# ME433_sunyue.net
KiCad netlist of a schematic drawn in EAGLE
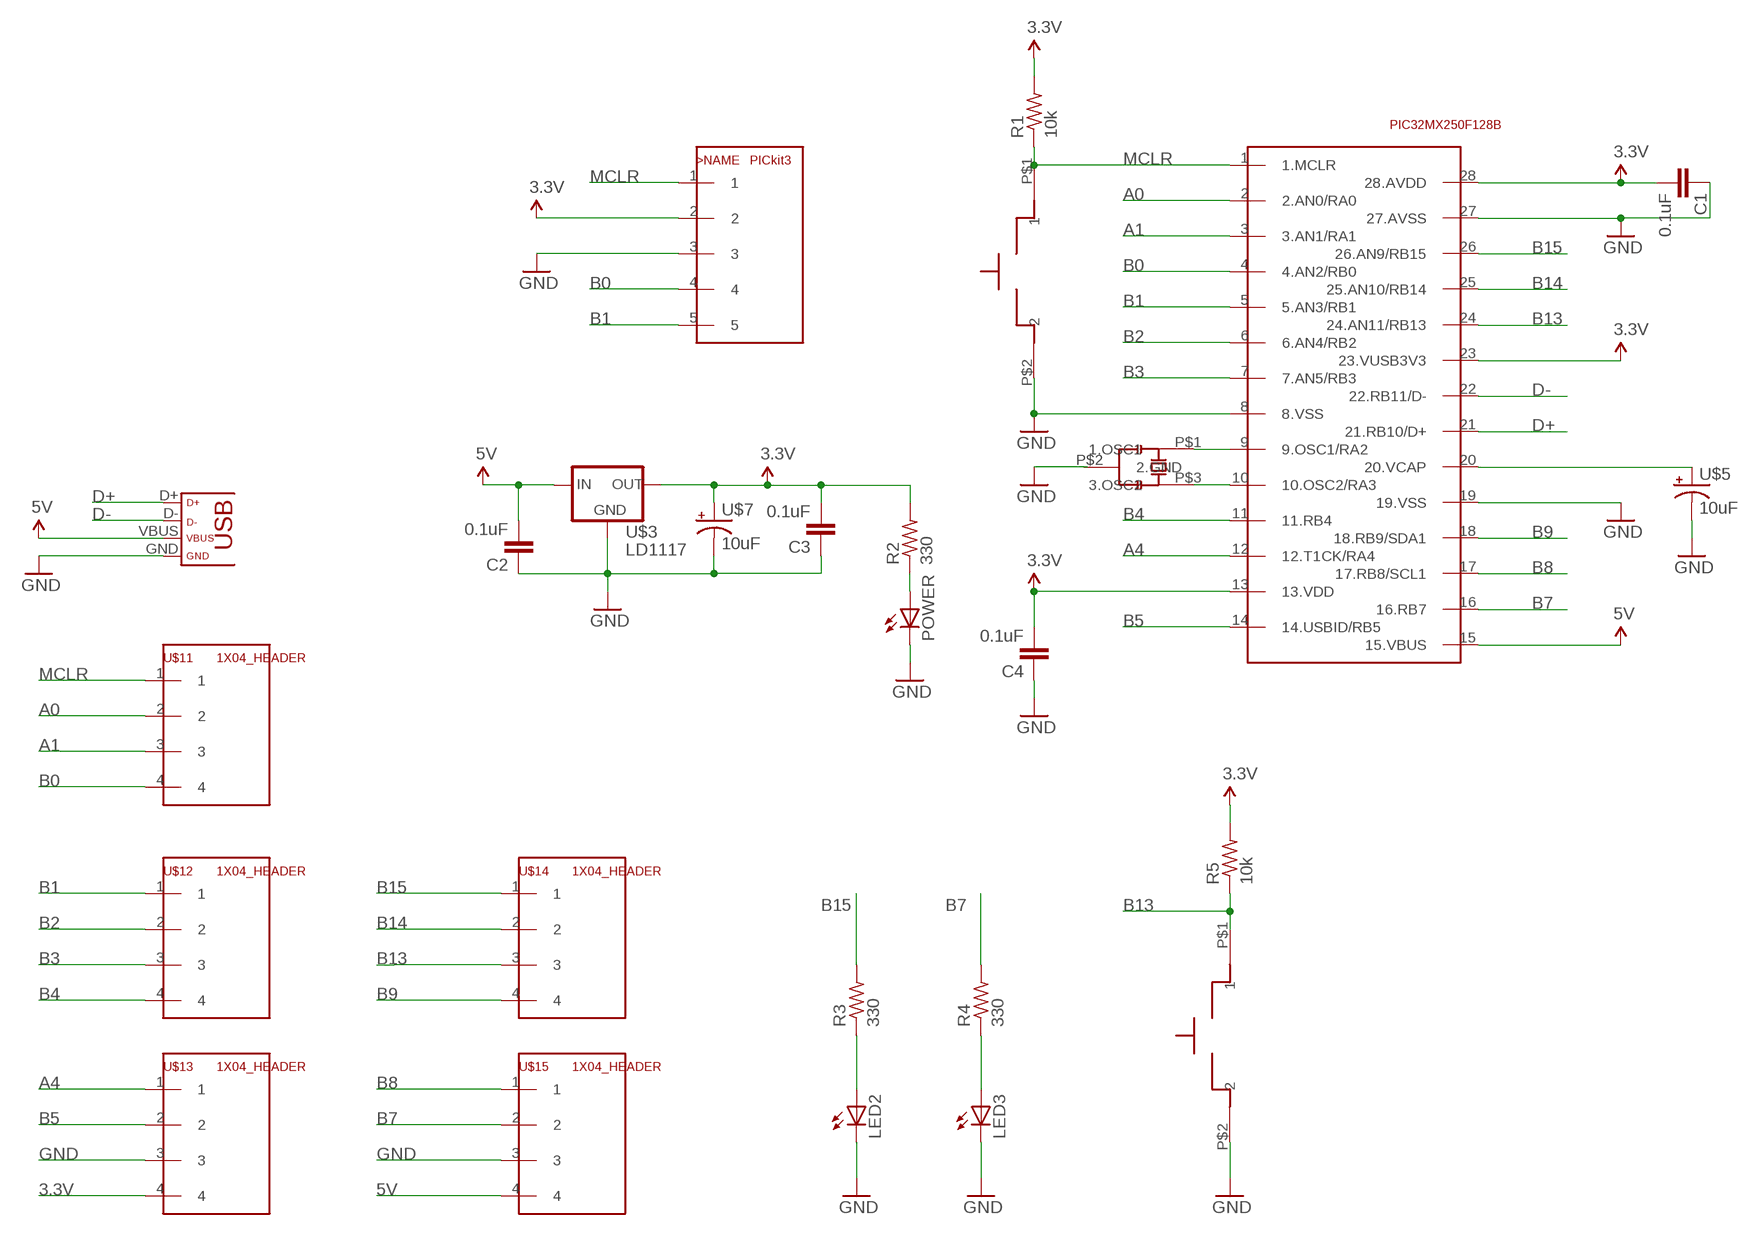
[diagram p0: schematic, sheet 1]

(export (version "E")
  (design (tool "Eeschema 10.0.6"))
  (components
    (comp (ref ">NAME")
      (value "PICkit3")
      (footprint "eagle-import:1X05")
      (libsource (lib "eagle-import") (part "1X05_HEADER"))
    )
    (comp (ref "C1")
      (value "0.1uF")
      (footprint "eagle-import:C025-025X050")
      (libsource (lib "eagle-import") (part "C-EU025-025X050"))
    )
    (comp (ref "C2")
      (value "0.1uF")
      (footprint "eagle-import:C025-025X050")
      (libsource (lib "eagle-import") (part "C-EU025-025X050"))
    )
    (comp (ref "C3")
      (value "0.1uF")
      (footprint "eagle-import:C025-025X050")
      (libsource (lib "eagle-import") (part "C-EU025-025X050"))
    )
    (comp (ref "C4")
      (value "0.1uF")
      (footprint "eagle-import:C025-025X050")
      (libsource (lib "eagle-import") (part "C-EU025-025X050"))
    )
    (comp (ref "LED2")
      (value "LED3MM")
      (footprint "eagle-import:LED3MM")
      (libsource (lib "eagle-import") (part "LED3MM"))
    )
    (comp (ref "LED3")
      (value "LED3MM")
      (footprint "eagle-import:LED3MM")
      (libsource (lib "eagle-import") (part "LED3MM"))
    )
    (comp (ref "POWER")
      (value "LED3MM")
      (footprint "eagle-import:LED3MM")
      (libsource (lib "eagle-import") (part "LED3MM"))
    )
    (comp (ref "R1")
      (value "10k")
      (footprint "eagle-import:0207_10")
      (libsource (lib "eagle-import") (part "R-US_0207/10"))
    )
    (comp (ref "R2")
      (value "330")
      (footprint "eagle-import:0207_10")
      (libsource (lib "eagle-import") (part "R-US_0207/10"))
    )
    (comp (ref "R3")
      (value "330")
      (footprint "eagle-import:0207_10")
      (libsource (lib "eagle-import") (part "R-US_0207/10"))
    )
    (comp (ref "R4")
      (value "330")
      (footprint "eagle-import:0207_10")
      (libsource (lib "eagle-import") (part "R-US_0207/10"))
    )
    (comp (ref "R5")
      (value "10k")
      (footprint "eagle-import:0207_10")
      (libsource (lib "eagle-import") (part "R-US_0207/10"))
    )
    (comp (ref "RESET")
      (value "RESET")
      (footprint "eagle-import:BUTTON")
      (libsource (lib "eagle-import") (part "BUTTON"))
    )
    (comp (ref "U$1")
      (value "PIC32MX250F128B")
      (footprint "eagle-import:DIL28-3")
      (libsource (lib "eagle-import") (part "PIC32MX250F128B"))
    )
    (comp (ref "U$2")
      (value "CRYSTAL")
      (footprint "eagle-import:CRYSTAL")
      (libsource (lib "eagle-import") (part "CRYSTAL"))
    )
    (comp (ref "U$3")
      (value "LD1117")
      (footprint "eagle-import:TO220")
      (libsource (lib "eagle-import") (part "LD1117"))
    )
    (comp (ref "U$5")
      (value "10uF")
      (footprint "eagle-import:CAP_POL_D")
      (libsource (lib "eagle-import") (part "CAP_POL"))
    )
    (comp (ref "U$7")
      (value "10uF")
      (footprint "eagle-import:CAP_POL_D")
      (libsource (lib "eagle-import") (part "CAP_POL"))
    )
    (comp (ref "U$9")
      (value "USB")
      (footprint "eagle-import:USB-MINIB")
      (libsource (lib "eagle-import") (part "USB"))
    )
    (comp (ref "U$11")
      (value "1X04_HEADER")
      (footprint "eagle-import:1X04")
      (libsource (lib "eagle-import") (part "1X04_HEADER"))
    )
    (comp (ref "U$12")
      (value "1X04_HEADER")
      (footprint "eagle-import:1X04")
      (libsource (lib "eagle-import") (part "1X04_HEADER"))
    )
    (comp (ref "U$13")
      (value "1X04_HEADER")
      (footprint "eagle-import:1X04")
      (libsource (lib "eagle-import") (part "1X04_HEADER"))
    )
    (comp (ref "U$14")
      (value "1X04_HEADER")
      (footprint "eagle-import:1X04")
      (libsource (lib "eagle-import") (part "1X04_HEADER"))
    )
    (comp (ref "U$15")
      (value "1X04_HEADER")
      (footprint "eagle-import:1X04")
      (libsource (lib "eagle-import") (part "1X04_HEADER"))
    )
    (comp (ref "USER")
      (value "BUTTON")
      (footprint "eagle-import:BUTTON")
      (libsource (lib "eagle-import") (part "BUTTON"))
    )
  )
  (nets
    (net (code "1") (name "/A0") (class "Default")
      (node (ref "U$1") (pin "2") (pinfunction "2.AN0/RA0_2") (pintype "bidirectional"))
      (node (ref "U$11") (pin "2") (pinfunction "2_2") (pintype "bidirectional"))
    )
    (net (code "2") (name "/A1") (class "Default")
      (node (ref "U$1") (pin "3") (pinfunction "3.AN1/RA1_3") (pintype "bidirectional"))
      (node (ref "U$11") (pin "3") (pinfunction "3_3") (pintype "bidirectional"))
    )
    (net (code "3") (name "/A4") (class "Default")
      (node (ref "U$1") (pin "12") (pinfunction "12.T1CK/RA4_12") (pintype "bidirectional"))
      (node (ref "U$13") (pin "1") (pinfunction "1_1") (pintype "bidirectional"))
    )
    (net (code "4") (name "/B0") (class "Default")
      (node (ref ">NAME") (pin "4") (pinfunction "4_4") (pintype "bidirectional"))
      (node (ref "U$1") (pin "4") (pinfunction "4.AN2/RB0_4") (pintype "bidirectional"))
      (node (ref "U$11") (pin "4") (pinfunction "4_4") (pintype "bidirectional"))
    )
    (net (code "5") (name "/B1") (class "Default")
      (node (ref ">NAME") (pin "5") (pinfunction "5_5") (pintype "bidirectional"))
      (node (ref "U$1") (pin "5") (pinfunction "5.AN3/RB1_5") (pintype "bidirectional"))
      (node (ref "U$12") (pin "1") (pinfunction "1_1") (pintype "bidirectional"))
    )
    (net (code "6") (name "/B2") (class "Default")
      (node (ref "U$1") (pin "6") (pinfunction "6.AN4/RB2_6") (pintype "bidirectional"))
      (node (ref "U$12") (pin "2") (pinfunction "2_2") (pintype "bidirectional"))
    )
    (net (code "7") (name "/B3") (class "Default")
      (node (ref "U$1") (pin "7") (pinfunction "7.AN5/RB3_7") (pintype "bidirectional"))
      (node (ref "U$12") (pin "3") (pinfunction "3_3") (pintype "bidirectional"))
    )
    (net (code "8") (name "/B4") (class "Default")
      (node (ref "U$1") (pin "11") (pinfunction "11.RB4_11") (pintype "bidirectional"))
      (node (ref "U$12") (pin "4") (pinfunction "4_4") (pintype "bidirectional"))
    )
    (net (code "9") (name "/B5") (class "Default")
      (node (ref "U$1") (pin "14") (pinfunction "14.USBID/RB5_14") (pintype "bidirectional"))
      (node (ref "U$13") (pin "2") (pinfunction "2_2") (pintype "bidirectional"))
    )
    (net (code "10") (name "/B7") (class "Default")
      (node (ref "R4") (pin "2") (pinfunction "2_2") (pintype "passive"))
      (node (ref "U$1") (pin "16") (pinfunction "16.RB7_16") (pintype "bidirectional"))
      (node (ref "U$15") (pin "2") (pinfunction "2_2") (pintype "bidirectional"))
    )
    (net (code "11") (name "/B8") (class "Default")
      (node (ref "U$1") (pin "17") (pinfunction "17.RB8/SCL1_17") (pintype "bidirectional"))
      (node (ref "U$15") (pin "1") (pinfunction "1_1") (pintype "bidirectional"))
    )
    (net (code "12") (name "/B9") (class "Default")
      (node (ref "U$1") (pin "18") (pinfunction "18.RB9/SDA1_18") (pintype "bidirectional"))
      (node (ref "U$14") (pin "4") (pinfunction "4_4") (pintype "bidirectional"))
    )
    (net (code "13") (name "/B13") (class "Default")
      (node (ref "R5") (pin "1") (pinfunction "1_1") (pintype "passive"))
      (node (ref "U$1") (pin "24") (pinfunction "24.AN11/RB13_24") (pintype "bidirectional"))
      (node (ref "U$14") (pin "3") (pinfunction "3_3") (pintype "bidirectional"))
      (node (ref "USER") (pin "P$1") (pinfunction "1_P$1") (pintype "bidirectional"))
    )
    (net (code "14") (name "/B14") (class "Default")
      (node (ref "U$1") (pin "25") (pinfunction "25.AN10/RB14_25") (pintype "bidirectional"))
      (node (ref "U$14") (pin "2") (pinfunction "2_2") (pintype "bidirectional"))
    )
    (net (code "15") (name "/B15") (class "Default")
      (node (ref "R3") (pin "2") (pinfunction "2_2") (pintype "passive"))
      (node (ref "U$1") (pin "26") (pinfunction "26.AN9/RB15_26") (pintype "bidirectional"))
      (node (ref "U$14") (pin "1") (pinfunction "1_1") (pintype "bidirectional"))
    )
    (net (code "16") (name "/D+") (class "Default")
      (node (ref "U$1") (pin "21") (pinfunction "21.RB10/D+_21") (pintype "bidirectional"))
      (node (ref "U$9") (pin "D+") (pinfunction "D+_D+") (pintype "bidirectional"))
    )
    (net (code "17") (name "/D-") (class "Default")
      (node (ref "U$1") (pin "22") (pinfunction "22.RB11/D-_22") (pintype "bidirectional"))
      (node (ref "U$9") (pin "D-") (pinfunction "D-_D-") (pintype "bidirectional"))
    )
    (net (code "18") (name "/MCLR") (class "Default")
      (node (ref ">NAME") (pin "1") (pinfunction "1_1") (pintype "bidirectional"))
      (node (ref "R1") (pin "1") (pinfunction "1_1") (pintype "passive"))
      (node (ref "RESET") (pin "P$1") (pinfunction "1_P$1") (pintype "bidirectional"))
      (node (ref "U$1") (pin "1") (pinfunction "1.MCLR_1") (pintype "bidirectional"))
      (node (ref "U$11") (pin "1") (pinfunction "1_1") (pintype "bidirectional"))
    )
    (net (code "19") (name "3.3V") (class "Default")
      (node (ref ">NAME") (pin "2") (pinfunction "2_2") (pintype "bidirectional"))
      (node (ref "C1") (pin "2") (pinfunction "2_2") (pintype "passive"))
      (node (ref "C3") (pin "2") (pinfunction "2_2") (pintype "passive"))
      (node (ref "C4") (pin "2") (pinfunction "2_2") (pintype "passive"))
      (node (ref "R1") (pin "2") (pinfunction "2_2") (pintype "passive"))
      (node (ref "R2") (pin "2") (pinfunction "2_2") (pintype "passive"))
      (node (ref "R5") (pin "2") (pinfunction "2_2") (pintype "passive"))
      (node (ref "U$1") (pin "13") (pinfunction "13.VDD_13") (pintype "bidirectional"))
      (node (ref "U$1") (pin "23") (pinfunction "23.VUSB3V3_23") (pintype "bidirectional"))
      (node (ref "U$1") (pin "28") (pinfunction "28.AVDD_28") (pintype "bidirectional"))
      (node (ref "U$13") (pin "4") (pinfunction "4_4") (pintype "bidirectional"))
      (node (ref "U$3") (pin "2") (pinfunction "OUT_2") (pintype "output"))
      (node (ref "U$7") (pin "1") (pinfunction "+_1") (pintype "passive"))
    )
    (net (code "20") (name "5V") (class "Default")
      (node (ref "C2") (pin "2") (pinfunction "2_2") (pintype "passive"))
      (node (ref "U$1") (pin "15") (pinfunction "15.VBUS_15") (pintype "bidirectional"))
      (node (ref "U$15") (pin "4") (pinfunction "4_4") (pintype "bidirectional"))
      (node (ref "U$3") (pin "3") (pinfunction "IN_3") (pintype "input"))
      (node (ref "U$9") (pin "VBUS") (pinfunction "VBUS_VBUS") (pintype "bidirectional"))
    )
    (net (code "21") (name "GND") (class "Default")
      (node (ref ">NAME") (pin "3") (pinfunction "3_3") (pintype "bidirectional"))
      (node (ref "C1") (pin "1") (pinfunction "1_1") (pintype "passive"))
      (node (ref "C2") (pin "1") (pinfunction "1_1") (pintype "passive"))
      (node (ref "C3") (pin "1") (pinfunction "1_1") (pintype "passive"))
      (node (ref "C4") (pin "1") (pinfunction "1_1") (pintype "passive"))
      (node (ref "LED2") (pin "K") (pinfunction "C_K") (pintype "passive"))
      (node (ref "LED3") (pin "K") (pinfunction "C_K") (pintype "passive"))
      (node (ref "POWER") (pin "K") (pinfunction "C_K") (pintype "passive"))
      (node (ref "RESET") (pin "P$2") (pinfunction "2_P$2") (pintype "bidirectional"))
      (node (ref "U$1") (pin "19") (pinfunction "19.VSS_19") (pintype "bidirectional"))
      (node (ref "U$1") (pin "27") (pinfunction "27.AVSS_27") (pintype "bidirectional"))
      (node (ref "U$1") (pin "8") (pinfunction "8.VSS_8") (pintype "bidirectional"))
      (node (ref "U$13") (pin "3") (pinfunction "3_3") (pintype "bidirectional"))
      (node (ref "U$15") (pin "3") (pinfunction "3_3") (pintype "bidirectional"))
      (node (ref "U$3") (pin "1") (pinfunction "GND_1") (pintype "input"))
      (node (ref "U$5") (pin "2") (pinfunction "-_2") (pintype "passive"))
      (node (ref "U$7") (pin "2") (pinfunction "-_2") (pintype "passive"))
      (node (ref "U$9") (pin "GND") (pinfunction "GND_GND") (pintype "bidirectional"))
      (node (ref "USER") (pin "P$2") (pinfunction "2_P$2") (pintype "bidirectional"))
    )
    (net (code "22") (name "Net-(LED2-PadA)") (class "Default")
      (node (ref "LED2") (pin "A") (pinfunction "A_A") (pintype "passive"))
      (node (ref "R3") (pin "1") (pinfunction "1_1") (pintype "passive"))
    )
    (net (code "23") (name "Net-(LED3-PadA)") (class "Default")
      (node (ref "LED3") (pin "A") (pinfunction "A_A") (pintype "passive"))
      (node (ref "R4") (pin "1") (pinfunction "1_1") (pintype "passive"))
    )
    (net (code "24") (name "Net-(POWER-PadA)") (class "Default")
      (node (ref "POWER") (pin "A") (pinfunction "A_A") (pintype "passive"))
      (node (ref "R2") (pin "1") (pinfunction "1_1") (pintype "passive"))
    )
    (net (code "25") (name "Net-(U$1-9.OSC1{slash}RA2)") (class "Default")
      (node (ref "U$1") (pin "9") (pinfunction "9.OSC1/RA2_9") (pintype "bidirectional"))
      (node (ref "U$2") (pin "P$1") (pinfunction "1.OSC1_P$1") (pintype "bidirectional"))
    )
    (net (code "26") (name "Net-(U$1-10.OSC2{slash}RA3)") (class "Default")
      (node (ref "U$1") (pin "10") (pinfunction "10.OSC2/RA3_10") (pintype "bidirectional"))
      (node (ref "U$2") (pin "P$3") (pinfunction "3.OSC2_P$3") (pintype "bidirectional"))
    )
    (net (code "27") (name "Net-(U$1-20.VCAP)") (class "Default")
      (node (ref "U$1") (pin "20") (pinfunction "20.VCAP_20") (pintype "bidirectional"))
      (node (ref "U$5") (pin "1") (pinfunction "+_1") (pintype "passive"))
    )
    (net (code "28") (name "unconnected-(U$2-2.GND-PadP$2)") (class "Default")
      (node (ref "U$2") (pin "P$2") (pinfunction "2.GND_P$2") (pintype "bidirectional"))
    )
  )
)
